# LickDetector_0_5_in.net
KiCad netlist of a schematic drawn in EAGLE
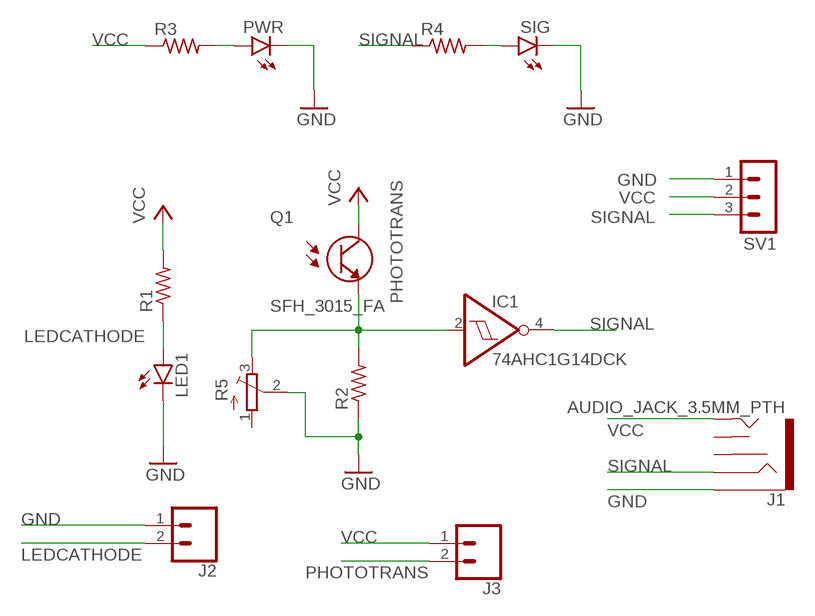
[diagram p0: schematic, sheet 1]

(export (version "E")
  (design (tool "Eeschema 10.0.6"))
  (components
    (comp (ref "IC1")
      (value "74AHC1G14DCK")
      (footprint "eagle-import:SC70-5")
      (libsource (lib "eagle-import") (part "741G14DCKAHC"))
    )
    (comp (ref "J1")
      (value "AUDIO_JACK_3.5MM_PTH")
      (footprint "eagle-import:AUDIO-JACK")
      (libsource (lib "eagle-import") (part "AUDIO_JACK_3.5MM_PTH"))
    )
    (comp (ref "J2")
      (value "CONN_02")
      (footprint "eagle-import:1X02")
      (libsource (lib "eagle-import") (part "CONN_02"))
    )
    (comp (ref "J3")
      (value "CONN_02")
      (footprint "eagle-import:1X02")
      (libsource (lib "eagle-import") (part "CONN_02"))
    )
    (comp (ref "LED1")
      (value "LEDCHIPLED_1206")
      (footprint "eagle-import:CHIPLED_1206")
      (libsource (lib "eagle-import") (part "LEDCHIPLED_1206"))
    )
    (comp (ref "PWR")
      (value "LEDCHIP-LED0603")
      (footprint "eagle-import:CHIP-LED0603")
      (libsource (lib "eagle-import") (part "LEDCHIP-LED0603"))
    )
    (comp (ref "Q1")
      (value "SFH_3015_FA")
      (footprint "eagle-import:XDCR_SFH_3015_FA")
      (fields
        (field (name "DIGI-KEY_PART_NUMBER") "475-2914-1-ND")
        (field (name "MF") "OSRAM Opto")
        (field (name "MP") "SFH 3015 FA")
      )
      (libsource (lib "eagle-import") (part "SFH_3015_FA"))
    )
    (comp (ref "R1")
      (value "R-US_R0603")
      (footprint "eagle-import:R0603")
      (libsource (lib "eagle-import") (part "R-US_R0603"))
    )
    (comp (ref "R2")
      (value "R-US_R0603")
      (footprint "eagle-import:R0603")
      (libsource (lib "eagle-import") (part "R-US_R0603"))
    )
    (comp (ref "R3")
      (value "R-US_R0603")
      (footprint "eagle-import:R0603")
      (libsource (lib "eagle-import") (part "R-US_R0603"))
    )
    (comp (ref "R4")
      (value "R-US_R0603")
      (footprint "eagle-import:R0603")
      (libsource (lib "eagle-import") (part "R-US_R0603"))
    )
    (comp (ref "R5")
      (value "TRIM_EU-3223J")
      (footprint "eagle-import:3223J")
      (libsource (lib "eagle-import") (part "TRIM_EU-3223J"))
    )
    (comp (ref "SIG")
      (value "LEDCHIP-LED0603")
      (footprint "eagle-import:CHIP-LED0603")
      (libsource (lib "eagle-import") (part "LEDCHIP-LED0603"))
    )
    (comp (ref "SV1")
      (value "MA03-1")
      (footprint "eagle-import:MA03-1")
      (libsource (lib "eagle-import") (part "MA03-1"))
    )
  )
  (nets
    (net (code "1") (name "/LEDCATHODE") (class "Default")
      (node (ref "J2") (pin "2") (pinfunction "2_2") (pintype "passive"))
      (node (ref "LED1") (pin "A") (pinfunction "A_A") (pintype "passive"))
      (node (ref "R1") (pin "1") (pinfunction "1_1") (pintype "passive"))
    )
    (net (code "2") (name "/PHOTOTRANS") (class "Default")
      (node (ref "IC1") (pin "2") (pinfunction "I_2") (pintype "input"))
      (node (ref "J3") (pin "2") (pinfunction "2_2") (pintype "passive"))
      (node (ref "Q1") (pin "1") (pinfunction "E_1") (pintype "passive"))
      (node (ref "R2") (pin "2") (pinfunction "2_2") (pintype "passive"))
      (node (ref "R5") (pin "3") (pinfunction "E_3") (pintype "passive"))
    )
    (net (code "3") (name "/SIGNAL") (class "Default")
      (node (ref "IC1") (pin "4") (pinfunction "O_4") (pintype "output"))
      (node (ref "J1") (pin "RING") (pinfunction "RING_RING") (pintype "bidirectional"))
      (node (ref "R4") (pin "1") (pinfunction "1_1") (pintype "passive"))
      (node (ref "SV1") (pin "3") (pinfunction "3_3") (pintype "passive"))
    )
    (net (code "4") (name "GND") (class "Default")
      (node (ref "J1") (pin "SLEEVE") (pinfunction "SLEEVE_SLEEVE") (pintype "bidirectional"))
      (node (ref "J2") (pin "1") (pinfunction "1_1") (pintype "passive"))
      (node (ref "LED1") (pin "C") (pinfunction "C_C") (pintype "passive"))
      (node (ref "PWR") (pin "C") (pinfunction "C_C") (pintype "passive"))
      (node (ref "R2") (pin "1") (pinfunction "1_1") (pintype "passive"))
      (node (ref "R5") (pin "2") (pinfunction "S_2") (pintype "passive"))
      (node (ref "SIG") (pin "C") (pinfunction "C_C") (pintype "passive"))
      (node (ref "SV1") (pin "1") (pinfunction "1_1") (pintype "passive"))
    )
    (net (code "5") (name "Net-(PWR-PadA)") (class "Default")
      (node (ref "PWR") (pin "A") (pinfunction "A_A") (pintype "passive"))
      (node (ref "R3") (pin "2") (pinfunction "2_2") (pintype "passive"))
    )
    (net (code "6") (name "Net-(R4-Pad2)") (class "Default")
      (node (ref "R4") (pin "2") (pinfunction "2_2") (pintype "passive"))
      (node (ref "SIG") (pin "A") (pinfunction "A_A") (pintype "passive"))
    )
    (net (code "7") (name "VCC") (class "Default")
      (node (ref "J1") (pin "TIP") (pinfunction "TIP_TIP") (pintype "bidirectional"))
      (node (ref "J3") (pin "1") (pinfunction "1_1") (pintype "passive"))
      (node (ref "Q1") (pin "2") (pinfunction "C_2") (pintype "passive"))
      (node (ref "R1") (pin "2") (pinfunction "2_2") (pintype "passive"))
      (node (ref "R3") (pin "1") (pinfunction "1_1") (pintype "passive"))
      (node (ref "SV1") (pin "2") (pinfunction "2_2") (pintype "passive"))
    )
    (net (code "8") (name "unconnected-(J1-PadRSH)") (class "Default")
      (node (ref "J1") (pin "RSH") (pinfunction "RSH_RSH") (pintype "bidirectional"))
    )
    (net (code "9") (name "unconnected-(J1-PadTSH)") (class "Default")
      (node (ref "J1") (pin "TSH") (pinfunction "TSH_TSH") (pintype "bidirectional"))
    )
    (net (code "10") (name "unconnected-(R5-A-Pad1)") (class "Default")
      (node (ref "R5") (pin "1") (pinfunction "A_1") (pintype "passive"))
    )
  )
)
